# Main.net
KiCad netlist of a schematic drawn in Altium Designer
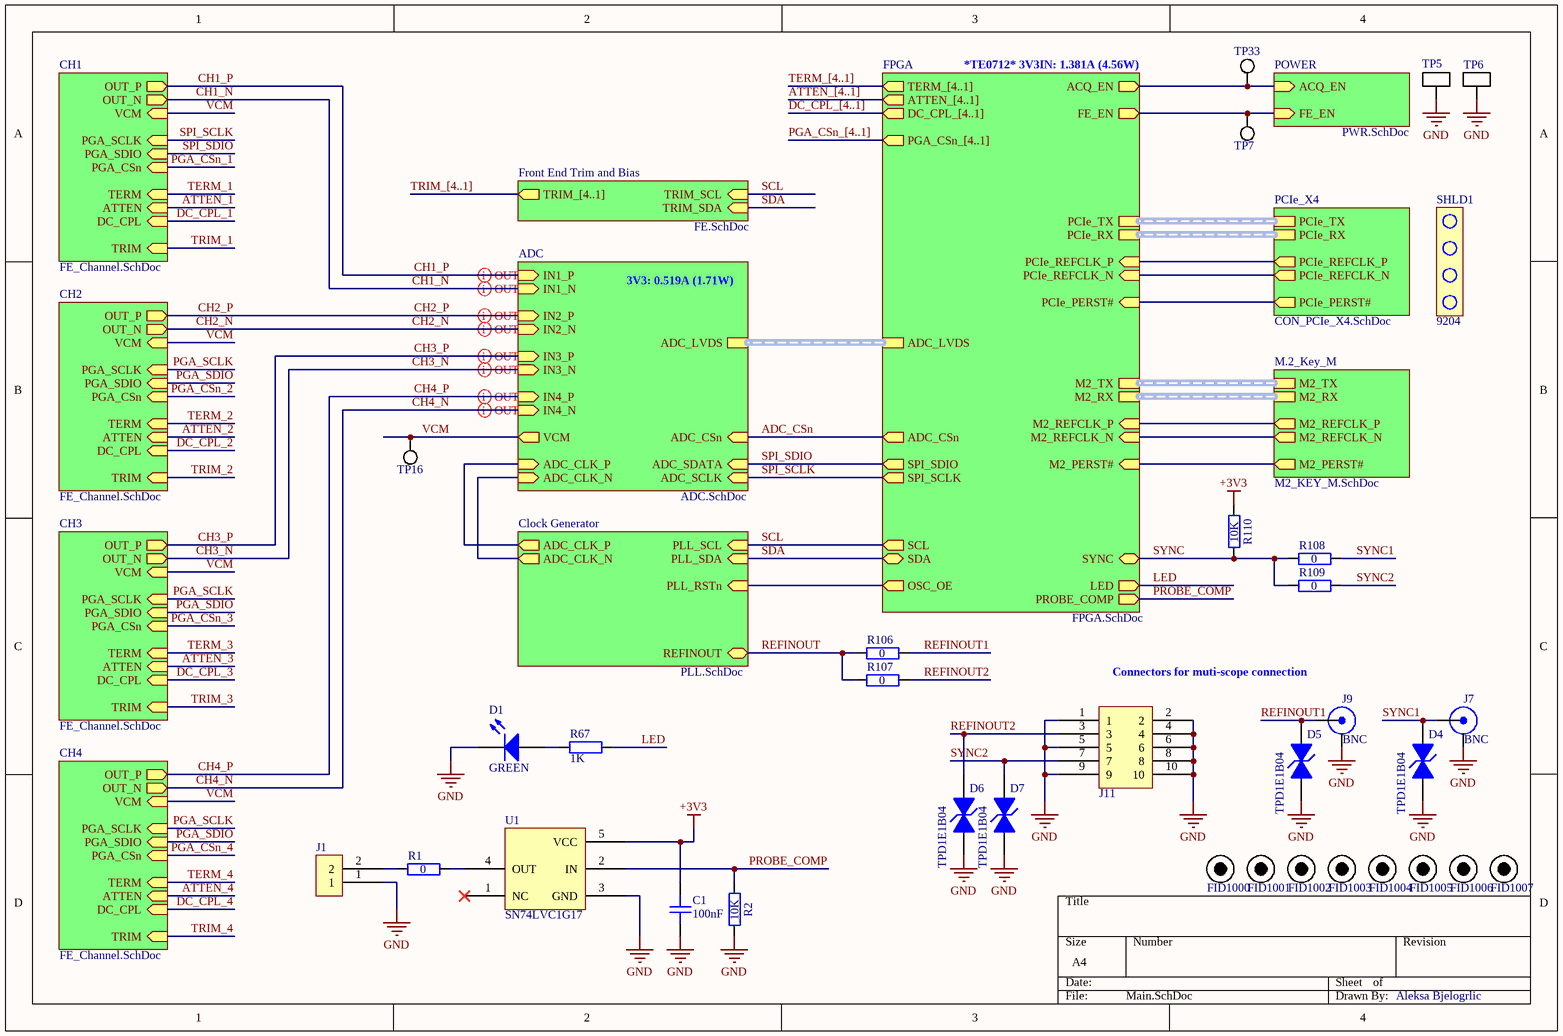
[diagram p0: Main.SchDoc]

(export (version "E")
  (design (tool "Eeschema 10.0.6"))
  (components
    (comp (ref "C1")
      (value "100nF")
      (footprint "GEN_C_0402")
      (fields
        (field (name "HOUSE PART NUMBER") "C-100nF-0402-002")
        (field (name "MANUFACTURER") "Murata")
        (field (name "MANUFACTURER PART NUMBER") "GCM155R71C104KA55D")
      )
      (libsource (lib "DSO") (part "CAP 100nF 16V X7R 0402"))
    )
    (comp (ref "D1")
      (value "GREEN")
      (footprint "LED_0603_LTST-S270K")
      (fields
        (field (name "MANUFACTURER") "Vishay Lite-On")
        (field (name "MANUFACTURER PART NUMBER") "LTST-S270KGKT")
      )
      (libsource (lib "DSO") (part "LED GREEN 0603 LTST-S270K"))
    )
    (comp (ref "D4")
      (value "TPD1E1B04")
      (footprint "TI_X1SON_DPY0002A")
      (fields
        (field (name "MANUFACTURER") "Texas Instruments")
        (field (name "MANUFACTURER PART NUMBER") "TPD1E1B04DPYR")
      )
      (libsource (lib "DSO") (part "TVS TPD1E1B04"))
    )
    (comp (ref "D5")
      (value "TPD1E1B04")
      (footprint "TI_X1SON_DPY0002A")
      (fields
        (field (name "MANUFACTURER") "Texas Instruments")
        (field (name "MANUFACTURER PART NUMBER") "TPD1E1B04DPYR")
      )
      (libsource (lib "DSO") (part "TVS TPD1E1B04"))
    )
    (comp (ref "D6")
      (value "TPD1E1B04")
      (footprint "TI_X1SON_DPY0002A")
      (fields
        (field (name "MANUFACTURER") "Texas Instruments")
        (field (name "MANUFACTURER PART NUMBER") "TPD1E1B04DPYR")
      )
      (libsource (lib "DSO") (part "TVS TPD1E1B04"))
    )
    (comp (ref "D7")
      (value "TPD1E1B04")
      (footprint "TI_X1SON_DPY0002A")
      (fields
        (field (name "MANUFACTURER") "Texas Instruments")
        (field (name "MANUFACTURER PART NUMBER") "TPD1E1B04DPYR")
      )
      (libsource (lib "DSO") (part "TVS TPD1E1B04"))
    )
    (comp (ref "FID1000")
      (value "PCB")
      (footprint "GEN_FID")
      (fields (field (name "HOUSE PART NUMBER") "Fiducial-1"))
      (libsource (lib "DSO") (part "FID 1mm"))
    )
    (comp (ref "FID1001")
      (value "PCB")
      (footprint "GEN_FID")
      (fields (field (name "HOUSE PART NUMBER") "Fiducial-1"))
      (libsource (lib "DSO") (part "FID 1mm"))
    )
    (comp (ref "FID1002")
      (value "PCB")
      (footprint "GEN_FID")
      (fields (field (name "HOUSE PART NUMBER") "Fiducial-1"))
      (libsource (lib "DSO") (part "FID 1mm"))
    )
    (comp (ref "FID1003")
      (value "PCB")
      (footprint "GEN_FID")
      (fields (field (name "HOUSE PART NUMBER") "Fiducial-1"))
      (libsource (lib "DSO") (part "FID 1mm"))
    )
    (comp (ref "FID1004")
      (value "PCB")
      (footprint "GEN_FID")
      (fields (field (name "HOUSE PART NUMBER") "Fiducial-1"))
      (libsource (lib "DSO") (part "FID 1mm"))
    )
    (comp (ref "FID1005")
      (value "PCB")
      (footprint "GEN_FID")
      (fields (field (name "HOUSE PART NUMBER") "Fiducial-1"))
      (libsource (lib "DSO") (part "FID 1mm"))
    )
    (comp (ref "FID1006")
      (value "PCB")
      (footprint "GEN_FID")
      (fields (field (name "HOUSE PART NUMBER") "Fiducial-1"))
      (libsource (lib "DSO") (part "FID 1mm"))
    )
    (comp (ref "FID1007")
      (value "PCB")
      (footprint "GEN_FID")
      (fields (field (name "HOUSE PART NUMBER") "Fiducial-1"))
      (libsource (lib "DSO") (part "FID 1mm"))
    )
    (comp (ref "J1")
      (value "TSW-101-08-F-D-RA")
      (footprint "GEN_2.54mm_1x2_Pin_TH_RA")
      (fields (field (name "MANUFACTURER") "Samtec"))
      (libsource (lib "DSO") (part "CONN 2.54mm 2 Pin TH RA"))
    )
    (comp (ref "J7")
      (value "BNC")
      (footprint "MOL_0731000105")
      (fields (field (name "MANUFACTURER") "Molex") (field (name "MANUFACTURER PART NUMBER") "73100-0105"))
      (libsource (lib "DSO") (part "BNC JACK R/A"))
    )
    (comp (ref "J9")
      (value "BNC")
      (footprint "MOL_0731000105")
      (fields (field (name "MANUFACTURER") "Molex") (field (name "MANUFACTURER PART NUMBER") "73100-0105"))
      (libsource (lib "DSO") (part "BNC JACK R/A"))
    )
    (comp (ref "J11")
      (value "1.27mm 6 Pin TH")
      (footprint "GEN_1.27mm_2x5_Pin_TH_RA")
      (fields
        (field (name "MANUFACTURER") "CNC Tech")
        (field (name "MANUFACTURER PART NUMBER") "3220-10-0200-00")
      )
      (libsource (lib "DSO") (part "CONN 1.27mm 2x5 Pin TH RA"))
    )
    (comp (ref "R1")
      (value "0")
      (footprint "GEN_R_0402")
      (fields
        (field (name "MANUFACTURER") "Yageo")
        (field (name "MANUFACTURER PART NUMBER") "RC0402JR-070RL")
      )
      (libsource (lib "") (part "RES 0 OHM 1/16W 0402_1"))
    )
    (comp (ref "R2")
      (value "10K")
      (footprint "GEN_R_0402")
      (fields
        (field (name "TOLERANCE") "1%")
        (field (name "MANUFACTURER") "Panasonic")
        (field (name "MANUFACTURER PART NUMBER") "ERJ-2RKF1002X")
      )
      (libsource (lib "DSO") (part "RES 10K OHM 1% 1/10W 0402"))
    )
    (comp (ref "R67")
      (value "1K")
      (footprint "GEN_R_0402")
      (fields
        (field (name "TOLERANCE") "1%")
        (field (name "HOUSE PART NUMBER") "R-1K-0402-1%-001")
        (field (name "MANUFACTURER") "Yageo")
      )
      (libsource (lib "DSO") (part "RES 1K OHM 1% 1/10W 0402"))
    )
    (comp (ref "R106")
      (value "0")
      (footprint "GEN_R_0402")
      (fields
        (field (name "MANUFACTURER") "Yageo")
        (field (name "MANUFACTURER PART NUMBER") "RC0402JR-070RL")
      )
      (libsource (lib "DSO") (part "RES 0 OHM 1/16W 0402"))
    )
    (comp (ref "R107")
      (value "0")
      (footprint "GEN_R_0402")
      (fields
        (field (name "MANUFACTURER") "Yageo")
        (field (name "MANUFACTURER PART NUMBER") "RC0402JR-070RL")
      )
      (libsource (lib "DSO") (part "RES 0 OHM 1/16W 0402"))
    )
    (comp (ref "R108")
      (value "0")
      (footprint "GEN_R_0402")
      (fields
        (field (name "MANUFACTURER") "Yageo")
        (field (name "MANUFACTURER PART NUMBER") "RC0402JR-070RL")
      )
      (libsource (lib "DSO") (part "RES 0 OHM 1/16W 0402"))
    )
    (comp (ref "R109")
      (value "0")
      (footprint "GEN_R_0402")
      (fields
        (field (name "MANUFACTURER") "Yageo")
        (field (name "MANUFACTURER PART NUMBER") "RC0402JR-070RL")
      )
      (libsource (lib "DSO") (part "RES 0 OHM 1/16W 0402"))
    )
    (comp (ref "R110")
      (value "10K")
      (footprint "GEN_R_0402")
      (fields
        (field (name "TOLERANCE") "1%")
        (field (name "MANUFACTURER") "Panasonic")
        (field (name "MANUFACTURER PART NUMBER") "ERJ-2RKF1002X")
      )
      (libsource (lib "") (part "RES 10K OHM 1% 1/10W 0402_1"))
    )
    (comp (ref "SHLD1")
      (value "9204")
      (fields (field (name "MANUFACTURER") "Keystone Electronics"))
      (libsource (lib "DSO") (part "PCIe IO Shield"))
    )
    (comp (ref "TP5")
      (value "5019")
      (footprint "KEY_5019")
      (fields (field (name "MANUFACTURER") "Keystone Electronics"))
      (libsource (lib "DSO") (part "TP KEYSTONE 5019"))
    )
    (comp (ref "TP6")
      (value "5019")
      (footprint "KEY_5019")
      (fields (field (name "MANUFACTURER") "Keystone Electronics"))
      (libsource (lib "DSO") (part "TP KEYSTONE 5019"))
    )
    (comp (ref "TP7") (value "PCB") (footprint "GEN_TP_PCB") (libsource (lib "DSO") (part "TP PCB 1mm")))
    (comp (ref "TP16") (value "PCB") (footprint "GEN_TP_PCB") (libsource (lib "DSO") (part "TP PCB 1mm")))
    (comp (ref "TP33") (value "PCB") (footprint "GEN_TP_PCB") (libsource (lib "DSO") (part "TP PCB 1mm")))
    (comp (ref "U1")
      (value "SN74LVC1G17")
      (footprint "GEN_SC-70-5")
      (fields
        (field (name "MANUFACTURER") "Texas Instruments")
        (field (name "MANUFACTURER PART NUMBER") "SN74LVC1G17DBVR")
      )
      (libsource (lib "DSO") (part "IC BUFFER SN74LVC1G17"))
    )
  )
  (nets
    (net (code "1") (name "+3V3") (class "Default")
      (node (ref "C1") (pin "1") (pinfunction "1_1") (pintype "passive"))
      (node (ref "R110") (pin "1") (pinfunction "1_1") (pintype "passive"))
      (node (ref "U1") (pin "5") (pinfunction "VCC_5") (pintype "passive"))
    )
    (net (code "2") (name "/ACQ_EN") (class "Default")
      (node (ref "TP33") (pin "1") (pinfunction "1_1") (pintype "passive"))
    )
    (net (code "25") (name "/FE_EN") (class "Default")
      (node (ref "TP7") (pin "1") (pinfunction "1_1") (pintype "passive"))
    )
    (net (code "26") (name "/LED") (class "Default")
      (node (ref "R67") (pin "2") (pinfunction "2_2") (pintype "passive"))
    )
    (net (code "45") (name "/PROBE_COMP") (class "Default")
      (node (ref "R2") (pin "2") (pinfunction "2_2") (pintype "passive"))
      (node (ref "U1") (pin "2") (pinfunction "IN_2") (pintype "passive"))
    )
    (net (code "46") (name "/REFINOUT") (class "Default")
      (node (ref "R106") (pin "2") (pinfunction "2_2") (pintype "passive"))
      (node (ref "R107") (pin "2") (pinfunction "2_2") (pintype "passive"))
    )
    (net (code "47") (name "/REFINOUT1") (class "Default")
      (node (ref "D5") (pin "1") (pinfunction "K_1") (pintype "passive"))
      (node (ref "J9") (pin "1") (pinfunction "Signal_1") (pintype "passive"))
      (node (ref "R106") (pin "1") (pinfunction "1_1") (pintype "passive"))
    )
    (net (code "48") (name "/REFINOUT2") (class "Default")
      (node (ref "D6") (pin "1") (pinfunction "K_1") (pintype "passive"))
      (node (ref "J11") (pin "3") (pinfunction "3_3") (pintype "passive"))
      (node (ref "R107") (pin "1") (pinfunction "1_1") (pintype "passive"))
    )
    (net (code "53") (name "/SYNC") (class "Default")
      (node (ref "R108") (pin "2") (pinfunction "2_2") (pintype "passive"))
      (node (ref "R109") (pin "2") (pinfunction "2_2") (pintype "passive"))
      (node (ref "R110") (pin "2") (pinfunction "2_2") (pintype "passive"))
    )
    (net (code "54") (name "/SYNC1") (class "Default")
      (node (ref "D4") (pin "1") (pinfunction "K_1") (pintype "passive"))
      (node (ref "J7") (pin "1") (pinfunction "Signal_1") (pintype "passive"))
      (node (ref "R108") (pin "1") (pinfunction "1_1") (pintype "passive"))
    )
    (net (code "55") (name "/SYNC2") (class "Default")
      (node (ref "D7") (pin "1") (pinfunction "K_1") (pintype "passive"))
      (node (ref "J11") (pin "7") (pinfunction "7_7") (pintype "passive"))
      (node (ref "R109") (pin "1") (pinfunction "1_1") (pintype "passive"))
    )
    (net (code "66") (name "/VCM") (class "Default")
      (node (ref "TP16") (pin "1") (pinfunction "1_1") (pintype "passive"))
    )
    (net (code "67") (name "GND") (class "Default")
      (node (ref "C1") (pin "2") (pinfunction "2_2") (pintype "passive"))
      (node (ref "D1") (pin "1") (pinfunction "K_1") (pintype "passive"))
      (node (ref "D4") (pin "2") (pinfunction "A_2") (pintype "passive"))
      (node (ref "D5") (pin "2") (pinfunction "A_2") (pintype "passive"))
      (node (ref "D6") (pin "2") (pinfunction "A_2") (pintype "passive"))
      (node (ref "D7") (pin "2") (pinfunction "A_2") (pintype "passive"))
      (node (ref "J1") (pin "1") (pinfunction "1_1") (pintype "passive"))
      (node (ref "J11") (pin "1") (pinfunction "1_1") (pintype "passive"))
      (node (ref "J11") (pin "10") (pinfunction "10_10") (pintype "passive"))
      (node (ref "J11") (pin "2") (pinfunction "2_2") (pintype "passive"))
      (node (ref "J11") (pin "4") (pinfunction "4_4") (pintype "passive"))
      (node (ref "J11") (pin "5") (pinfunction "5_5") (pintype "passive"))
      (node (ref "J11") (pin "6") (pinfunction "6_6") (pintype "passive"))
      (node (ref "J11") (pin "8") (pinfunction "8_8") (pintype "passive"))
      (node (ref "J11") (pin "9") (pinfunction "9_9") (pintype "passive"))
      (node (ref "J7") (pin "2") (pinfunction "SHIELD_2") (pintype "passive"))
      (node (ref "J9") (pin "2") (pinfunction "SHIELD_2") (pintype "passive"))
      (node (ref "R2") (pin "1") (pinfunction "1_1") (pintype "passive"))
      (node (ref "TP5") (pin "1") (pinfunction "1_1") (pintype "passive"))
      (node (ref "TP6") (pin "1") (pinfunction "1_1") (pintype "passive"))
      (node (ref "U1") (pin "3") (pinfunction "GND_3") (pintype "passive"))
    )
    (net (code "68") (name "Net-(D1-A)") (class "Default")
      (node (ref "D1") (pin "2") (pinfunction "A_2") (pintype "passive"))
      (node (ref "R67") (pin "1") (pinfunction "1_1") (pintype "passive"))
    )
    (net (code "69") (name "Net-(J1-Pad2)") (class "Default")
      (node (ref "J1") (pin "2") (pinfunction "2_2") (pintype "passive"))
      (node (ref "R1") (pin "1") (pinfunction "1_1") (pintype "passive"))
    )
    (net (code "70") (name "Net-(U1-OUT)") (class "Default")
      (node (ref "R1") (pin "2") (pinfunction "2_2") (pintype "passive"))
      (node (ref "U1") (pin "4") (pinfunction "OUT_4") (pintype "passive"))
    )
    (net (code "71") (name "unconnected-(U1-NC-Pad1)") (class "Default")
      (node (ref "U1") (pin "1") (pinfunction "NC_1") (pintype "passive+no_connect"))
    )
  )
)
